# button.net
KiCad netlist of a schematic drawn in Altium Designer
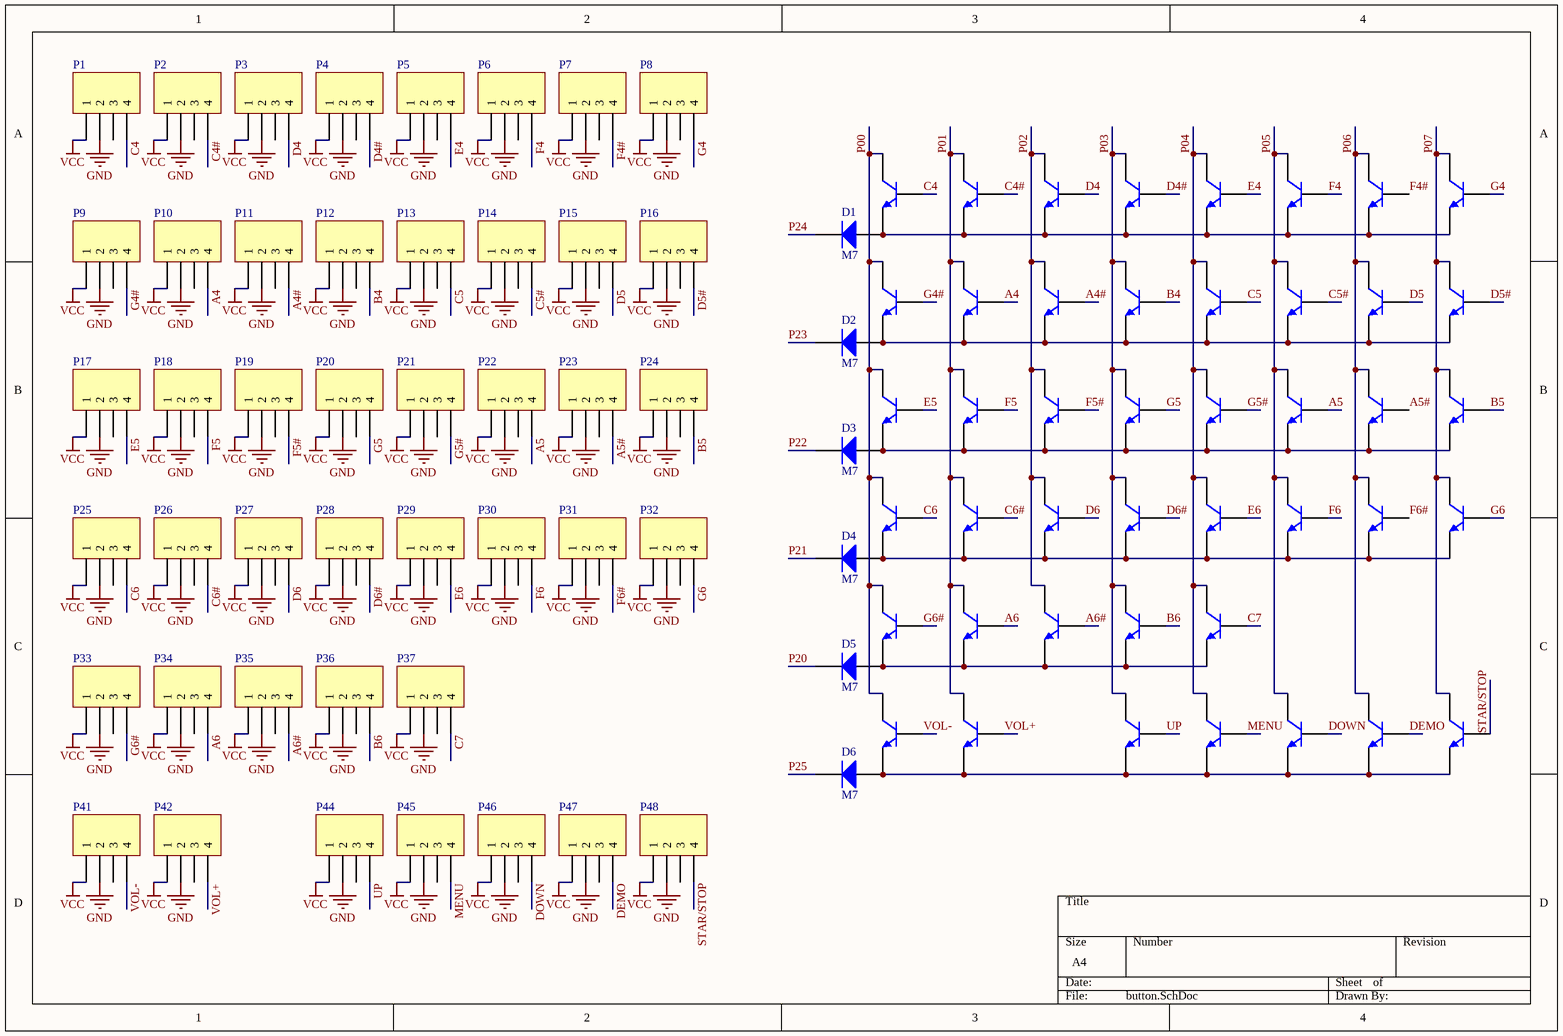
[diagram p0: button.SchDoc]

(export (version "E")
  (design (tool "Eeschema 10.0.6"))
  (components
    (comp (ref "D1")
      (value "M7")
      (footprint "SMA(DO-214AC)_S1")
      (description "二极管")
      (libsource (lib "Miscellaneous Devices LC") (part "SMA(DO-214AC) M7"))
    )
    (comp (ref "D2")
      (value "M7")
      (footprint "SMA(DO-214AC)_S1")
      (description "二极管")
      (libsource (lib "Miscellaneous Devices LC") (part "SMA(DO-214AC) M7"))
    )
    (comp (ref "D3")
      (value "M7")
      (footprint "SMA(DO-214AC)_S1")
      (description "二极管")
      (libsource (lib "Miscellaneous Devices LC") (part "SMA(DO-214AC) M7"))
    )
    (comp (ref "D4")
      (value "M7")
      (footprint "SMA(DO-214AC)_S1")
      (description "二极管")
      (libsource (lib "Miscellaneous Devices LC") (part "SMA(DO-214AC) M7"))
    )
    (comp (ref "D5")
      (value "M7")
      (footprint "SMA(DO-214AC)_S1")
      (description "二极管")
      (libsource (lib "Miscellaneous Devices LC") (part "SMA(DO-214AC) M7"))
    )
    (comp (ref "D6")
      (value "M7")
      (footprint "SMA(DO-214AC)_S1")
      (description "二极管")
      (libsource (lib "Miscellaneous Devices LC") (part "SMA(DO-214AC) M7"))
    )
    (comp (ref "P1")
      (value "Header 4")
      (footprint "FPC1.0-2H-WS-4P")
      (description "Header, 4-Pin")
      (fields (field (name "PUBLISHER") "Altium Limited"))
      (libsource (lib "Miscellaneous Connectors") (part "Header 4"))
    )
    (comp (ref "P2")
      (value "Header 4")
      (footprint "FPC1.0-2H-WS-4P")
      (description "Header, 4-Pin")
      (fields (field (name "PUBLISHER") "Altium Limited"))
      (libsource (lib "Miscellaneous Connectors") (part "Header 4"))
    )
    (comp (ref "P3")
      (value "Header 4")
      (footprint "FPC1.0-2H-WS-4P")
      (description "Header, 4-Pin")
      (fields (field (name "PUBLISHER") "Altium Limited"))
      (libsource (lib "Miscellaneous Connectors") (part "Header 4"))
    )
    (comp (ref "P4")
      (value "Header 4")
      (footprint "FPC1.0-2H-WS-4P")
      (description "Header, 4-Pin")
      (fields (field (name "PUBLISHER") "Altium Limited"))
      (libsource (lib "Miscellaneous Connectors") (part "Header 4"))
    )
    (comp (ref "P5")
      (value "Header 4")
      (footprint "FPC1.0-2H-WS-4P")
      (description "Header, 4-Pin")
      (fields (field (name "PUBLISHER") "Altium Limited"))
      (libsource (lib "Miscellaneous Connectors") (part "Header 4"))
    )
    (comp (ref "P6")
      (value "Header 4")
      (footprint "FPC1.0-2H-WS-4P")
      (description "Header, 4-Pin")
      (fields (field (name "PUBLISHER") "Altium Limited"))
      (libsource (lib "Miscellaneous Connectors") (part "Header 4"))
    )
    (comp (ref "P7")
      (value "Header 4")
      (footprint "FPC1.0-2H-WS-4P")
      (description "Header, 4-Pin")
      (fields (field (name "PUBLISHER") "Altium Limited"))
      (libsource (lib "Miscellaneous Connectors") (part "Header 4"))
    )
    (comp (ref "P8")
      (value "Header 4")
      (footprint "FPC1.0-2H-WS-4P")
      (description "Header, 4-Pin")
      (fields (field (name "PUBLISHER") "Altium Limited"))
      (libsource (lib "Miscellaneous Connectors") (part "Header 4"))
    )
    (comp (ref "P9")
      (value "Header 4")
      (footprint "FPC1.0-2H-WS-4P")
      (description "Header, 4-Pin")
      (fields (field (name "PUBLISHER") "Altium Limited"))
      (libsource (lib "Miscellaneous Connectors") (part "Header 4"))
    )
    (comp (ref "P10")
      (value "Header 4")
      (footprint "FPC1.0-2H-WS-4P")
      (description "Header, 4-Pin")
      (fields (field (name "PUBLISHER") "Altium Limited"))
      (libsource (lib "Miscellaneous Connectors") (part "Header 4"))
    )
    (comp (ref "P11")
      (value "Header 4")
      (footprint "FPC1.0-2H-WS-4P")
      (description "Header, 4-Pin")
      (fields (field (name "PUBLISHER") "Altium Limited"))
      (libsource (lib "Miscellaneous Connectors") (part "Header 4"))
    )
    (comp (ref "P12")
      (value "Header 4")
      (footprint "FPC1.0-2H-WS-4P")
      (description "Header, 4-Pin")
      (fields (field (name "PUBLISHER") "Altium Limited"))
      (libsource (lib "Miscellaneous Connectors") (part "Header 4"))
    )
    (comp (ref "P13")
      (value "Header 4")
      (footprint "FPC1.0-2H-WS-4P")
      (description "Header, 4-Pin")
      (fields (field (name "PUBLISHER") "Altium Limited"))
      (libsource (lib "Miscellaneous Connectors") (part "Header 4"))
    )
    (comp (ref "P14")
      (value "Header 4")
      (footprint "FPC1.0-2H-WS-4P")
      (description "Header, 4-Pin")
      (fields (field (name "PUBLISHER") "Altium Limited"))
      (libsource (lib "Miscellaneous Connectors") (part "Header 4"))
    )
    (comp (ref "P15")
      (value "Header 4")
      (footprint "FPC1.0-2H-WS-4P")
      (description "Header, 4-Pin")
      (fields (field (name "PUBLISHER") "Altium Limited"))
      (libsource (lib "Miscellaneous Connectors") (part "Header 4"))
    )
    (comp (ref "P16")
      (value "Header 4")
      (footprint "FPC1.0-2H-WS-4P")
      (description "Header, 4-Pin")
      (fields (field (name "PUBLISHER") "Altium Limited"))
      (libsource (lib "Miscellaneous Connectors") (part "Header 4"))
    )
    (comp (ref "P17")
      (value "Header 4")
      (footprint "FPC1.0-2H-WS-4P")
      (description "Header, 4-Pin")
      (fields (field (name "PUBLISHER") "Altium Limited"))
      (libsource (lib "Miscellaneous Connectors") (part "Header 4"))
    )
    (comp (ref "P18")
      (value "Header 4")
      (footprint "FPC1.0-2H-WS-4P")
      (description "Header, 4-Pin")
      (fields (field (name "PUBLISHER") "Altium Limited"))
      (libsource (lib "Miscellaneous Connectors") (part "Header 4"))
    )
    (comp (ref "P19")
      (value "Header 4")
      (footprint "FPC1.0-2H-WS-4P")
      (description "Header, 4-Pin")
      (fields (field (name "PUBLISHER") "Altium Limited"))
      (libsource (lib "Miscellaneous Connectors") (part "Header 4"))
    )
    (comp (ref "P20")
      (value "Header 4")
      (footprint "FPC1.0-2H-WS-4P")
      (description "Header, 4-Pin")
      (fields (field (name "PUBLISHER") "Altium Limited"))
      (libsource (lib "Miscellaneous Connectors") (part "Header 4"))
    )
    (comp (ref "P21")
      (value "Header 4")
      (footprint "FPC1.0-2H-WS-4P")
      (description "Header, 4-Pin")
      (fields (field (name "PUBLISHER") "Altium Limited"))
      (libsource (lib "Miscellaneous Connectors") (part "Header 4"))
    )
    (comp (ref "P22")
      (value "Header 4")
      (footprint "FPC1.0-2H-WS-4P")
      (description "Header, 4-Pin")
      (fields (field (name "PUBLISHER") "Altium Limited"))
      (libsource (lib "Miscellaneous Connectors") (part "Header 4"))
    )
    (comp (ref "P23")
      (value "Header 4")
      (footprint "FPC1.0-2H-WS-4P")
      (description "Header, 4-Pin")
      (fields (field (name "PUBLISHER") "Altium Limited"))
      (libsource (lib "Miscellaneous Connectors") (part "Header 4"))
    )
    (comp (ref "P24")
      (value "Header 4")
      (footprint "FPC1.0-2H-WS-4P")
      (description "Header, 4-Pin")
      (fields (field (name "PUBLISHER") "Altium Limited"))
      (libsource (lib "Miscellaneous Connectors") (part "Header 4"))
    )
    (comp (ref "P25")
      (value "Header 4")
      (footprint "FPC1.0-2H-WS-4P")
      (description "Header, 4-Pin")
      (fields (field (name "PUBLISHER") "Altium Limited"))
      (libsource (lib "Miscellaneous Connectors") (part "Header 4"))
    )
    (comp (ref "P26")
      (value "Header 4")
      (footprint "FPC1.0-2H-WS-4P")
      (description "Header, 4-Pin")
      (fields (field (name "PUBLISHER") "Altium Limited"))
      (libsource (lib "Miscellaneous Connectors") (part "Header 4"))
    )
    (comp (ref "P27")
      (value "Header 4")
      (footprint "FPC1.0-2H-WS-4P")
      (description "Header, 4-Pin")
      (fields (field (name "PUBLISHER") "Altium Limited"))
      (libsource (lib "Miscellaneous Connectors") (part "Header 4"))
    )
    (comp (ref "P28")
      (value "Header 4")
      (footprint "FPC1.0-2H-WS-4P")
      (description "Header, 4-Pin")
      (fields (field (name "PUBLISHER") "Altium Limited"))
      (libsource (lib "Miscellaneous Connectors") (part "Header 4"))
    )
    (comp (ref "P29")
      (value "Header 4")
      (footprint "FPC1.0-2H-WS-4P")
      (description "Header, 4-Pin")
      (fields (field (name "PUBLISHER") "Altium Limited"))
      (libsource (lib "Miscellaneous Connectors") (part "Header 4"))
    )
    (comp (ref "P30")
      (value "Header 4")
      (footprint "FPC1.0-2H-WS-4P")
      (description "Header, 4-Pin")
      (fields (field (name "PUBLISHER") "Altium Limited"))
      (libsource (lib "Miscellaneous Connectors") (part "Header 4"))
    )
    (comp (ref "P31")
      (value "Header 4")
      (footprint "FPC1.0-2H-WS-4P")
      (description "Header, 4-Pin")
      (fields (field (name "PUBLISHER") "Altium Limited"))
      (libsource (lib "Miscellaneous Connectors") (part "Header 4"))
    )
    (comp (ref "P32")
      (value "Header 4")
      (footprint "FPC1.0-2H-WS-4P")
      (description "Header, 4-Pin")
      (fields (field (name "PUBLISHER") "Altium Limited"))
      (libsource (lib "Miscellaneous Connectors") (part "Header 4"))
    )
    (comp (ref "P33")
      (value "Header 4")
      (footprint "FPC1.0-2H-WS-4P")
      (description "Header, 4-Pin")
      (fields (field (name "PUBLISHER") "Altium Limited"))
      (libsource (lib "Miscellaneous Connectors") (part "Header 4"))
    )
    (comp (ref "P34")
      (value "Header 4")
      (footprint "FPC1.0-2H-WS-4P")
      (description "Header, 4-Pin")
      (fields (field (name "PUBLISHER") "Altium Limited"))
      (libsource (lib "Miscellaneous Connectors") (part "Header 4"))
    )
    (comp (ref "P35")
      (value "Header 4")
      (footprint "FPC1.0-2H-WS-4P")
      (description "Header, 4-Pin")
      (fields (field (name "PUBLISHER") "Altium Limited"))
      (libsource (lib "Miscellaneous Connectors") (part "Header 4"))
    )
    (comp (ref "P36")
      (value "Header 4")
      (footprint "FPC1.0-2H-WS-4P")
      (description "Header, 4-Pin")
      (fields (field (name "PUBLISHER") "Altium Limited"))
      (libsource (lib "Miscellaneous Connectors") (part "Header 4"))
    )
    (comp (ref "P37")
      (value "Header 4")
      (footprint "FPC1.0-2H-WS-4P")
      (description "Header, 4-Pin")
      (fields (field (name "PUBLISHER") "Altium Limited"))
      (libsource (lib "Miscellaneous Connectors") (part "Header 4"))
    )
    (comp (ref "P41")
      (value "Header 4")
      (footprint "FPC1.0-2H-WS-4P")
      (description "Header, 4-Pin")
      (fields (field (name "PUBLISHER") "Altium Limited"))
      (libsource (lib "Miscellaneous Connectors") (part "Header 4"))
    )
    (comp (ref "P42")
      (value "Header 4")
      (footprint "FPC1.0-2H-WS-4P")
      (description "Header, 4-Pin")
      (fields (field (name "PUBLISHER") "Altium Limited"))
      (libsource (lib "Miscellaneous Connectors") (part "Header 4"))
    )
    (comp (ref "P44")
      (value "Header 4")
      (footprint "FPC1.0-2H-WS-4P")
      (description "Header, 4-Pin")
      (fields (field (name "PUBLISHER") "Altium Limited"))
      (libsource (lib "Miscellaneous Connectors") (part "Header 4"))
    )
    (comp (ref "P45")
      (value "Header 4")
      (footprint "FPC1.0-2H-WS-4P")
      (description "Header, 4-Pin")
      (fields (field (name "PUBLISHER") "Altium Limited"))
      (libsource (lib "Miscellaneous Connectors") (part "Header 4"))
    )
    (comp (ref "P46")
      (value "Header 4")
      (footprint "FPC1.0-2H-WS-4P")
      (description "Header, 4-Pin")
      (fields (field (name "PUBLISHER") "Altium Limited"))
      (libsource (lib "Miscellaneous Connectors") (part "Header 4"))
    )
    (comp (ref "P47")
      (value "Header 4")
      (footprint "FPC1.0-2H-WS-4P")
      (description "Header, 4-Pin")
      (fields (field (name "PUBLISHER") "Altium Limited"))
      (libsource (lib "Miscellaneous Connectors") (part "Header 4"))
    )
    (comp (ref "P48")
      (value "Header 4")
      (footprint "FPC1.0-2H-WS-4P")
      (description "Header, 4-Pin")
      (fields (field (name "PUBLISHER") "Altium Limited"))
      (libsource (lib "Miscellaneous Connectors") (part "Header 4"))
    )
    (comp (ref "Q1")
      (value "SS8050 Y1")
      (footprint "SOT-23(SOT-23-3)")
      (description "三极管")
      (libsource (lib "Miscellaneous Devices LC") (part "SOT-23 SS8050 Y1"))
    )
    (comp (ref "Q2")
      (value "SS8050 Y1")
      (footprint "SOT-23(SOT-23-3)")
      (description "三极管")
      (libsource (lib "Miscellaneous Devices LC") (part "SOT-23 SS8050 Y1"))
    )
    (comp (ref "Q3")
      (value "SS8050 Y1")
      (footprint "SOT-23(SOT-23-3)")
      (description "三极管")
      (libsource (lib "Miscellaneous Devices LC") (part "SOT-23 SS8050 Y1"))
    )
    (comp (ref "Q4")
      (value "SS8050 Y1")
      (footprint "SOT-23(SOT-23-3)")
      (description "三极管")
      (libsource (lib "Miscellaneous Devices LC") (part "SOT-23 SS8050 Y1"))
    )
    (comp (ref "Q5")
      (value "SS8050 Y1")
      (footprint "SOT-23(SOT-23-3)")
      (description "三极管")
      (libsource (lib "Miscellaneous Devices LC") (part "SOT-23 SS8050 Y1"))
    )
    (comp (ref "Q6")
      (value "SS8050 Y1")
      (footprint "SOT-23(SOT-23-3)")
      (description "三极管")
      (libsource (lib "Miscellaneous Devices LC") (part "SOT-23 SS8050 Y1"))
    )
    (comp (ref "Q7")
      (value "SS8050 Y1")
      (footprint "SOT-23(SOT-23-3)")
      (description "三极管")
      (libsource (lib "Miscellaneous Devices LC") (part "SOT-23 SS8050 Y1"))
    )
    (comp (ref "Q8")
      (value "SS8050 Y1")
      (footprint "SOT-23(SOT-23-3)")
      (description "三极管")
      (libsource (lib "Miscellaneous Devices LC") (part "SOT-23 SS8050 Y1"))
    )
    (comp (ref "Q9")
      (value "SS8050 Y1")
      (footprint "SOT-23(SOT-23-3)")
      (description "三极管")
      (libsource (lib "Miscellaneous Devices LC") (part "SOT-23 SS8050 Y1"))
    )
    (comp (ref "Q10")
      (value "SS8050 Y1")
      (footprint "SOT-23(SOT-23-3)")
      (description "三极管")
      (libsource (lib "Miscellaneous Devices LC") (part "SOT-23 SS8050 Y1"))
    )
    (comp (ref "Q11")
      (value "SS8050 Y1")
      (footprint "SOT-23(SOT-23-3)")
      (description "三极管")
      (libsource (lib "Miscellaneous Devices LC") (part "SOT-23 SS8050 Y1"))
    )
    (comp (ref "Q12")
      (value "SS8050 Y1")
      (footprint "SOT-23(SOT-23-3)")
      (description "三极管")
      (libsource (lib "Miscellaneous Devices LC") (part "SOT-23 SS8050 Y1"))
    )
    (comp (ref "Q13")
      (value "SS8050 Y1")
      (footprint "SOT-23(SOT-23-3)")
      (description "三极管")
      (libsource (lib "Miscellaneous Devices LC") (part "SOT-23 SS8050 Y1"))
    )
    (comp (ref "Q14")
      (value "SS8050 Y1")
      (footprint "SOT-23(SOT-23-3)")
      (description "三极管")
      (libsource (lib "Miscellaneous Devices LC") (part "SOT-23 SS8050 Y1"))
    )
    (comp (ref "Q15")
      (value "SS8050 Y1")
      (footprint "SOT-23(SOT-23-3)")
      (description "三极管")
      (libsource (lib "Miscellaneous Devices LC") (part "SOT-23 SS8050 Y1"))
    )
    (comp (ref "Q16")
      (value "SS8050 Y1")
      (footprint "SOT-23(SOT-23-3)")
      (description "三极管")
      (libsource (lib "Miscellaneous Devices LC") (part "SOT-23 SS8050 Y1"))
    )
    (comp (ref "Q17")
      (value "SS8050 Y1")
      (footprint "SOT-23(SOT-23-3)")
      (description "三极管")
      (libsource (lib "Miscellaneous Devices LC") (part "SOT-23 SS8050 Y1"))
    )
    (comp (ref "Q18")
      (value "SS8050 Y1")
      (footprint "SOT-23(SOT-23-3)")
      (description "三极管")
      (libsource (lib "Miscellaneous Devices LC") (part "SOT-23 SS8050 Y1"))
    )
    (comp (ref "Q19")
      (value "SS8050 Y1")
      (footprint "SOT-23(SOT-23-3)")
      (description "三极管")
      (libsource (lib "Miscellaneous Devices LC") (part "SOT-23 SS8050 Y1"))
    )
    (comp (ref "Q20")
      (value "SS8050 Y1")
      (footprint "SOT-23(SOT-23-3)")
      (description "三极管")
      (libsource (lib "Miscellaneous Devices LC") (part "SOT-23 SS8050 Y1"))
    )
    (comp (ref "Q21")
      (value "SS8050 Y1")
      (footprint "SOT-23(SOT-23-3)")
      (description "三极管")
      (libsource (lib "Miscellaneous Devices LC") (part "SOT-23 SS8050 Y1"))
    )
    (comp (ref "Q22")
      (value "SS8050 Y1")
      (footprint "SOT-23(SOT-23-3)")
      (description "三极管")
      (libsource (lib "Miscellaneous Devices LC") (part "SOT-23 SS8050 Y1"))
    )
    (comp (ref "Q23")
      (value "SS8050 Y1")
      (footprint "SOT-23(SOT-23-3)")
      (description "三极管")
      (libsource (lib "Miscellaneous Devices LC") (part "SOT-23 SS8050 Y1"))
    )
    (comp (ref "Q24")
      (value "SS8050 Y1")
      (footprint "SOT-23(SOT-23-3)")
      (description "三极管")
      (libsource (lib "Miscellaneous Devices LC") (part "SOT-23 SS8050 Y1"))
    )
    (comp (ref "Q25")
      (value "SS8050 Y1")
      (footprint "SOT-23(SOT-23-3)")
      (description "三极管")
      (libsource (lib "Miscellaneous Devices LC") (part "SOT-23 SS8050 Y1"))
    )
    (comp (ref "Q26")
      (value "SS8050 Y1")
      (footprint "SOT-23(SOT-23-3)")
      (description "三极管")
      (libsource (lib "Miscellaneous Devices LC") (part "SOT-23 SS8050 Y1"))
    )
    (comp (ref "Q27")
      (value "SS8050 Y1")
      (footprint "SOT-23(SOT-23-3)")
      (description "三极管")
      (libsource (lib "Miscellaneous Devices LC") (part "SOT-23 SS8050 Y1"))
    )
    (comp (ref "Q28")
      (value "SS8050 Y1")
      (footprint "SOT-23(SOT-23-3)")
      (description "三极管")
      (libsource (lib "Miscellaneous Devices LC") (part "SOT-23 SS8050 Y1"))
    )
    (comp (ref "Q29")
      (value "SS8050 Y1")
      (footprint "SOT-23(SOT-23-3)")
      (description "三极管")
      (libsource (lib "Miscellaneous Devices LC") (part "SOT-23 SS8050 Y1"))
    )
    (comp (ref "Q30")
      (value "SS8050 Y1")
      (footprint "SOT-23(SOT-23-3)")
      (description "三极管")
      (libsource (lib "Miscellaneous Devices LC") (part "SOT-23 SS8050 Y1"))
    )
    (comp (ref "Q31")
      (value "SS8050 Y1")
      (footprint "SOT-23(SOT-23-3)")
      (description "三极管")
      (libsource (lib "Miscellaneous Devices LC") (part "SOT-23 SS8050 Y1"))
    )
    (comp (ref "Q32")
      (value "SS8050 Y1")
      (footprint "SOT-23(SOT-23-3)")
      (description "三极管")
      (libsource (lib "Miscellaneous Devices LC") (part "SOT-23 SS8050 Y1"))
    )
    (comp (ref "Q33")
      (value "SS8050 Y1")
      (footprint "SOT-23(SOT-23-3)")
      (description "三极管")
      (libsource (lib "Miscellaneous Devices LC") (part "SOT-23 SS8050 Y1"))
    )
    (comp (ref "Q34")
      (value "SS8050 Y1")
      (footprint "SOT-23(SOT-23-3)")
      (description "三极管")
      (libsource (lib "Miscellaneous Devices LC") (part "SOT-23 SS8050 Y1"))
    )
    (comp (ref "Q35")
      (value "SS8050 Y1")
      (footprint "SOT-23(SOT-23-3)")
      (description "三极管")
      (libsource (lib "Miscellaneous Devices LC") (part "SOT-23 SS8050 Y1"))
    )
    (comp (ref "Q36")
      (value "SS8050 Y1")
      (footprint "SOT-23(SOT-23-3)")
      (description "三极管")
      (libsource (lib "Miscellaneous Devices LC") (part "SOT-23 SS8050 Y1"))
    )
    (comp (ref "Q37")
      (value "SS8050 Y1")
      (footprint "SOT-23(SOT-23-3)")
      (description "三极管")
      (libsource (lib "Miscellaneous Devices LC") (part "SOT-23 SS8050 Y1"))
    )
    (comp (ref "Q38")
      (value "SS8050 Y1")
      (footprint "SOT-23(SOT-23-3)")
      (description "三极管")
      (libsource (lib "Miscellaneous Devices LC") (part "SOT-23 SS8050 Y1"))
    )
    (comp (ref "Q39")
      (value "SS8050 Y1")
      (footprint "SOT-23(SOT-23-3)")
      (description "三极管")
      (libsource (lib "Miscellaneous Devices LC") (part "SOT-23 SS8050 Y1"))
    )
    (comp (ref "Q40")
      (value "SS8050 Y1")
      (footprint "SOT-23(SOT-23-3)")
      (description "三极管")
      (libsource (lib "Miscellaneous Devices LC") (part "SOT-23 SS8050 Y1"))
    )
    (comp (ref "Q41")
      (value "SS8050 Y1")
      (footprint "SOT-23(SOT-23-3)")
      (description "三极管")
      (libsource (lib "Miscellaneous Devices LC") (part "SOT-23 SS8050 Y1"))
    )
    (comp (ref "Q42")
      (value "SS8050 Y1")
      (footprint "SOT-23(SOT-23-3)")
      (description "三极管")
      (libsource (lib "Miscellaneous Devices LC") (part "SOT-23 SS8050 Y1"))
    )
    (comp (ref "Q43")
      (value "SS8050 Y1")
      (footprint "SOT-23(SOT-23-3)")
      (description "三极管")
      (libsource (lib "Miscellaneous Devices LC") (part "SOT-23 SS8050 Y1"))
    )
    (comp (ref "Q44")
      (value "SS8050 Y1")
      (footprint "SOT-23(SOT-23-3)")
      (description "三极管")
      (libsource (lib "Miscellaneous Devices LC") (part "SOT-23 SS8050 Y1"))
    )
  )
  (nets
    (net (code "1") (name "/A4") (class "Default")
      (node (ref "P10") (pin "4") (pinfunction "4_4") (pintype "passive"))
      (node (ref "Q10") (pin "1") (pinfunction "B_1") (pintype "passive"))
    )
    (net (code "2") (name "/A4#") (class "Default")
      (node (ref "P11") (pin "4") (pinfunction "4_4") (pintype "passive"))
      (node (ref "Q11") (pin "1") (pinfunction "B_1") (pintype "passive"))
    )
    (net (code "3") (name "/A5") (class "Default")
      (node (ref "P22") (pin "4") (pinfunction "4_4") (pintype "passive"))
      (node (ref "Q22") (pin "1") (pinfunction "B_1") (pintype "passive"))
    )
    (net (code "4") (name "/A5#") (class "Default")
      (node (ref "P23") (pin "4") (pinfunction "4_4") (pintype "passive"))
      (node (ref "Q23") (pin "1") (pinfunction "B_1") (pintype "passive"))
    )
    (net (code "5") (name "/A6") (class "Default")
      (node (ref "P34") (pin "4") (pinfunction "4_4") (pintype "passive"))
      (node (ref "Q34") (pin "1") (pinfunction "B_1") (pintype "passive"))
    )
    (net (code "6") (name "/A6#") (class "Default")
      (node (ref "P35") (pin "4") (pinfunction "4_4") (pintype "passive"))
      (node (ref "Q35") (pin "1") (pinfunction "B_1") (pintype "passive"))
    )
    (net (code "7") (name "/B4") (class "Default")
      (node (ref "P12") (pin "4") (pinfunction "4_4") (pintype "passive"))
      (node (ref "Q12") (pin "1") (pinfunction "B_1") (pintype "passive"))
    )
    (net (code "8") (name "/B5") (class "Default")
      (node (ref "P24") (pin "4") (pinfunction "4_4") (pintype "passive"))
      (node (ref "Q24") (pin "1") (pinfunction "B_1") (pintype "passive"))
    )
    (net (code "9") (name "/B6") (class "Default")
      (node (ref "P36") (pin "4") (pinfunction "4_4") (pintype "passive"))
      (node (ref "Q36") (pin "1") (pinfunction "B_1") (pintype "passive"))
    )
    (net (code "10") (name "/C4") (class "Default")
      (node (ref "P1") (pin "4") (pinfunction "4_4") (pintype "passive"))
      (node (ref "Q1") (pin "1") (pinfunction "B_1") (pintype "passive"))
    )
    (net (code "11") (name "/C4#") (class "Default")
      (node (ref "P2") (pin "4") (pinfunction "4_4") (pintype "passive"))
      (node (ref "Q2") (pin "1") (pinfunction "B_1") (pintype "passive"))
    )
    (net (code "12") (name "/C5") (class "Default")
      (node (ref "P13") (pin "4") (pinfunction "4_4") (pintype "passive"))
      (node (ref "Q13") (pin "1") (pinfunction "B_1") (pintype "passive"))
    )
    (net (code "13") (name "/C5#") (class "Default")
      (node (ref "P14") (pin "4") (pinfunction "4_4") (pintype "passive"))
      (node (ref "Q14") (pin "1") (pinfunction "B_1") (pintype "passive"))
    )
    (net (code "14") (name "/C6") (class "Default")
      (node (ref "P25") (pin "4") (pinfunction "4_4") (pintype "passive"))
      (node (ref "Q25") (pin "1") (pinfunction "B_1") (pintype "passive"))
    )
    (net (code "15") (name "/C6#") (class "Default")
      (node (ref "P26") (pin "4") (pinfunction "4_4") (pintype "passive"))
      (node (ref "Q26") (pin "1") (pinfunction "B_1") (pintype "passive"))
    )
    (net (code "16") (name "/C7") (class "Default")
      (node (ref "P37") (pin "4") (pinfunction "4_4") (pintype "passive"))
      (node (ref "Q37") (pin "1") (pinfunction "B_1") (pintype "passive"))
    )
    (net (code "17") (name "/D4") (class "Default")
      (node (ref "P3") (pin "4") (pinfunction "4_4") (pintype "passive"))
      (node (ref "Q3") (pin "1") (pinfunction "B_1") (pintype "passive"))
    )
    (net (code "18") (name "/D4#") (class "Default")
      (node (ref "P4") (pin "4") (pinfunction "4_4") (pintype "passive"))
      (node (ref "Q4") (pin "1") (pinfunction "B_1") (pintype "passive"))
    )
    (net (code "19") (name "/D5") (class "Default")
      (node (ref "P15") (pin "4") (pinfunction "4_4") (pintype "passive"))
      (node (ref "Q15") (pin "1") (pinfunction "B_1") (pintype "passive"))
    )
    (net (code "20") (name "/D5#") (class "Default")
      (node (ref "P16") (pin "4") (pinfunction "4_4") (pintype "passive"))
      (node (ref "Q16") (pin "1") (pinfunction "B_1") (pintype "passive"))
    )
    (net (code "21") (name "/D6") (class "Default")
      (node (ref "P27") (pin "4") (pinfunction "4_4") (pintype "passive"))
      (node (ref "Q27") (pin "1") (pinfunction "B_1") (pintype "passive"))
    )
    (net (code "22") (name "/D6#") (class "Default")
      (node (ref "P28") (pin "4") (pinfunction "4_4") (pintype "passive"))
      (node (ref "Q28") (pin "1") (pinfunction "B_1") (pintype "passive"))
    )
    (net (code "23") (name "/DEMO") (class "Default")
      (node (ref "P47") (pin "4") (pinfunction "4_4") (pintype "passive"))
      (node (ref "Q43") (pin "1") (pinfunction "B_1") (pintype "passive"))
    )
    (net (code "24") (name "/DOWN") (class "Default")
      (node (ref "P46") (pin "4") (pinfunction "4_4") (pintype "passive"))
      (node (ref "Q42") (pin "1") (pinfunction "B_1") (pintype "passive"))
    )
    (net (code "25") (name "/E4") (class "Default")
      (node (ref "P5") (pin "4") (pinfunction "4_4") (pintype "passive"))
      (node (ref "Q5") (pin "1") (pinfunction "B_1") (pintype "passive"))
    )
    (net (code "26") (name "/E5") (class "Default")
      (node (ref "P17") (pin "4") (pinfunction "4_4") (pintype "passive"))
      (node (ref "Q17") (pin "1") (pinfunction "B_1") (pintype "passive"))
    )
    (net (code "27") (name "/E6") (class "Default")
      (node (ref "P29") (pin "4") (pinfunction "4_4") (pintype "passive"))
      (node (ref "Q29") (pin "1") (pinfunction "B_1") (pintype "passive"))
    )
    (net (code "28") (name "/F4") (class "Default")
      (node (ref "P6") (pin "4") (pinfunction "4_4") (pintype "passive"))
      (node (ref "Q6") (pin "1") (pinfunction "B_1") (pintype "passive"))
    )
    (net (code "29") (name "/F4#") (class "Default")
      (node (ref "P7") (pin "4") (pinfunction "4_4") (pintype "passive"))
      (node (ref "Q7") (pin "1") (pinfunction "B_1") (pintype "passive"))
    )
    (net (code "30") (name "/F5") (class "Default")
      (node (ref "P18") (pin "4") (pinfunction "4_4") (pintype "passive"))
      (node (ref "Q18") (pin "1") (pinfunction "B_1") (pintype "passive"))
    )
    (net (code "31") (name "/F5#") (class "Default")
      (node (ref "P19") (pin "4") (pinfunction "4_4") (pintype "passive"))
      (node (ref "Q19") (pin "1") (pinfunction "B_1") (pintype "passive"))
    )
    (net (code "32") (name "/F6") (class "Default")
      (node (ref "P30") (pin "4") (pinfunction "4_4") (pintype "passive"))
      (node (ref "Q30") (pin "1") (pinfunction "B_1") (pintype "passive"))
    )
    (net (code "33") (name "/F6#") (class "Default")
      (node (ref "P31") (pin "4") (pinfunction "4_4") (pintype "passive"))
      (node (ref "Q31") (pin "1") (pinfunction "B_1") (pintype "passive"))
    )
    (net (code "34") (name "/G4") (class "Default")
      (node (ref "P8") (pin "4") (pinfunction "4_4") (pintype "passive"))
      (node (ref "Q8") (pin "1") (pinfunction "B_1") (pintype "passive"))
    )
    (net (code "35") (name "/G4#") (class "Default")
      (node (ref "P9") (pin "4") (pinfunction "4_4") (pintype "passive"))
      (node (ref "Q9") (pin "1") (pinfunction "B_1") (pintype "passive"))
    )
    (net (code "36") (name "/G5") (class "Default")
      (node (ref "P20") (pin "4") (pinfunction "4_4") (pintype "passive"))
      (node (ref "Q20") (pin "1") (pinfunction "B_1") (pintype "passive"))
    )
    (net (code "37") (name "/G5#") (class "Default")
      (node (ref "P21") (pin "4") (pinfunction "4_4") (pintype "passive"))
      (node (ref "Q21") (pin "1") (pinfunction "B_1") (pintype "passive"))
    )
    (net (code "38") (name "/G6") (class "Default")
      (node (ref "P32") (pin "4") (pinfunction "4_4") (pintype "passive"))
      (node (ref "Q32") (pin "1") (pinfunction "B_1") (pintype "passive"))
    )
    (net (code "39") (name "/G6#") (class "Default")
      (node (ref "P33") (pin "4") (pinfunction "4_4") (pintype "passive"))
      (node (ref "Q33") (pin "1") (pinfunction "B_1") (pintype "passive"))
    )
    (net (code "40") (name "/MENU") (class "Default")
      (node (ref "P45") (pin "4") (pinfunction "4_4") (pintype "passive"))
      (node (ref "Q41") (pin "1") (pinfunction "B_1") (pintype "passive"))
    )
    (net (code "41") (name "/P00") (class "Default")
      (node (ref "Q1") (pin "3") (pinfunction "C_3") (pintype "passive"))
      (node (ref "Q17") (pin "3") (pinfunction "C_3") (pintype "passive"))
      (node (ref "Q25") (pin "3") (pinfunction "C_3") (pintype "passive"))
      (node (ref "Q33") (pin "3") (pinfunction "C_3") (pintype "passive"))
      (node (ref "Q38") (pin "3") (pinfunction "C_3") (pintype "passive"))
      (node (ref "Q9") (pin "3") (pinfunction "C_3") (pintype "passive"))
    )
    (net (code "42") (name "/P01") (class "Default")
      (node (ref "Q10") (pin "3") (pinfunction "C_3") (pintype "passive"))
      (node (ref "Q18") (pin "3") (pinfunction "C_3") (pintype "passive"))
      (node (ref "Q2") (pin "3") (pinfunction "C_3") (pintype "passive"))
      (node (ref "Q26") (pin "3") (pinfunction "C_3") (pintype "passive"))
      (node (ref "Q34") (pin "3") (pinfunction "C_3") (pintype "passive"))
      (node (ref "Q39") (pin "3") (pinfunction "C_3") (pintype "passive"))
    )
    (net (code "43") (name "/P02") (class "Default")
      (node (ref "Q11") (pin "3") (pinfunction "C_3") (pintype "passive"))
      (node (ref "Q19") (pin "3") (pinfunction "C_3") (pintype "passive"))
      (node (ref "Q27") (pin "3") (pinfunction "C_3") (pintype "passive"))
      (node (ref "Q3") (pin "3") (pinfunction "C_3") (pintype "passive"))
      (node (ref "Q35") (pin "3") (pinfunction "C_3") (pintype "passive"))
    )
    (net (code "44") (name "/P03") (class "Default")
      (node (ref "Q12") (pin "3") (pinfunction "C_3") (pintype "passive"))
      (node (ref "Q20") (pin "3") (pinfunction "C_3") (pintype "passive"))
      (node (ref "Q28") (pin "3") (pinfunction "C_3") (pintype "passive"))
      (node (ref "Q36") (pin "3") (pinfunction "C_3") (pintype "passive"))
      (node (ref "Q4") (pin "3") (pinfunction "C_3") (pintype "passive"))
      (node (ref "Q40") (pin "3") (pinfunction "C_3") (pintype "passive"))
    )
    (net (code "45") (name "/P04") (class "Default")
      (node (ref "Q13") (pin "3") (pinfunction "C_3") (pintype "passive"))
      (node (ref "Q21") (pin "3") (pinfunction "C_3") (pintype "passive"))
      (node (ref "Q29") (pin "3") (pinfunction "C_3") (pintype "passive"))
      (node (ref "Q37") (pin "3") (pinfunction "C_3") (pintype "passive"))
      (node (ref "Q41") (pin "3") (pinfunction "C_3") (pintype "passive"))
      (node (ref "Q5") (pin "3") (pinfunction "C_3") (pintype "passive"))
    )
    (net (code "46") (name "/P05") (class "Default")
      (node (ref "Q14") (pin "3") (pinfunction "C_3") (pintype "passive"))
      (node (ref "Q22") (pin "3") (pinfunction "C_3") (pintype "passive"))
      (node (ref "Q30") (pin "3") (pinfunction "C_3") (pintype "passive"))
      (node (ref "Q42") (pin "3") (pinfunction "C_3") (pintype "passive"))
      (node (ref "Q6") (pin "3") (pinfunction "C_3") (pintype "passive"))
    )
    (net (code "47") (name "/P06") (class "Default")
      (node (ref "Q15") (pin "3") (pinfunction "C_3") (pintype "passive"))
      (node (ref "Q23") (pin "3") (pinfunction "C_3") (pintype "passive"))
      (node (ref "Q31") (pin "3") (pinfunction "C_3") (pintype "passive"))
      (node (ref "Q43") (pin "3") (pinfunction "C_3") (pintype "passive"))
      (node (ref "Q7") (pin "3") (pinfunction "C_3") (pintype "passive"))
    )
    (net (code "48") (name "/P07") (class "Default")
      (node (ref "Q16") (pin "3") (pinfunction "C_3") (pintype "passive"))
      (node (ref "Q24") (pin "3") (pinfunction "C_3") (pintype "passive"))
      (node (ref "Q32") (pin "3") (pinfunction "C_3") (pintype "passive"))
      (node (ref "Q44") (pin "3") (pinfunction "C_3") (pintype "passive"))
      (node (ref "Q8") (pin "3") (pinfunction "C_3") (pintype "passive"))
    )
    (net (code "49") (name "/P20") (class "Default")
      (node (ref "D5") (pin "2") (pinfunction "K_2") (pintype "passive"))
    )
    (net (code "50") (name "/P21") (class "Default")
      (node (ref "D4") (pin "2") (pinfunction "K_2") (pintype "passive"))
    )
    (net (code "51") (name "/P22") (class "Default")
      (node (ref "D3") (pin "2") (pinfunction "K_2") (pintype "passive"))
    )
    (net (code "52") (name "/P23") (class "Default")
      (node (ref "D2") (pin "2") (pinfunction "K_2") (pintype "passive"))
    )
    (net (code "53") (name "/P24") (class "Default")
      (node (ref "D1") (pin "2") (pinfunction "K_2") (pintype "passive"))
    )
    (net (code "54") (name "/P25") (class "Default")
      (node (ref "D6") (pin "2") (pinfunction "K_2") (pintype "passive"))
    )
    (net (code "55") (name "/STAR{slash}STOP") (class "Default")
      (node (ref "P48") (pin "4") (pinfunction "4_4") (pintype "passive"))
      (node (ref "Q44") (pin "1") (pinfunction "B_1") (pintype "passive"))
    )
    (net (code "56") (name "/UP") (class "Default")
      (node (ref "P44") (pin "4") (pinfunction "4_4") (pintype "passive"))
      (node (ref "Q40") (pin "1") (pinfunction "B_1") (pintype "passive"))
    )
    (net (code "57") (name "/VOL+") (class "Default")
      (node (ref "P42") (pin "4") (pinfunction "4_4") (pintype "passive"))
      (node (ref "Q39") (pin "1") (pinfunction "B_1") (pintype "passive"))
    )
    (net (code "58") (name "/VOL-") (class "Default")
      (node (ref "P41") (pin "4") (pinfunction "4_4") (pintype "passive"))
      (node (ref "Q38") (pin "1") (pinfunction "B_1") (pintype "passive"))
    )
    (net (code "59") (name "GND") (class "Default")
      (node (ref "P1") (pin "2") (pinfunction "2_2") (pintype "passive"))
      (node (ref "P10") (pin "2") (pinfunction "2_2") (pintype "passive"))
      (node (ref "P11") (pin "2") (pinfunction "2_2") (pintype "passive"))
      (node (ref "P12") (pin "2") (pinfunction "2_2") (pintype "passive"))
      (node (ref "P13") (pin "2") (pinfunction "2_2") (pintype "passive"))
      (node (ref "P14") (pin "2") (pinfunction "2_2") (pintype "passive"))
      (node (ref "P15") (pin "2") (pinfunction "2_2") (pintype "passive"))
      (node (ref "P16") (pin "2") (pinfunction "2_2") (pintype "passive"))
      (node (ref "P17") (pin "2") (pinfunction "2_2") (pintype "passive"))
      (node (ref "P18") (pin "2") (pinfunction "2_2") (pintype "passive"))
      (node (ref "P19") (pin "2") (pinfunction "2_2") (pintype "passive"))
      (node (ref "P2") (pin "2") (pinfunction "2_2") (pintype "passive"))
      (node (ref "P20") (pin "2") (pinfunction "2_2") (pintype "passive"))
      (node (ref "P21") (pin "2") (pinfunction "2_2") (pintype "passive"))
      (node (ref "P22") (pin "2") (pinfunction "2_2") (pintype "passive"))
      (node (ref "P23") (pin "2") (pinfunction "2_2") (pintype "passive"))
      (node (ref "P24") (pin "2") (pinfunction "2_2") (pintype "passive"))
      (node (ref "P25") (pin "2") (pinfunction "2_2") (pintype "passive"))
      (node (ref "P26") (pin "2") (pinfunction "2_2") (pintype "passive"))
      (node (ref "P27") (pin "2") (pinfunction "2_2") (pintype "passive"))
      (node (ref "P28") (pin "2") (pinfunction "2_2") (pintype "passive"))
      (node (ref "P29") (pin "2") (pinfunction "2_2") (pintype "passive"))
      (node (ref "P3") (pin "2") (pinfunction "2_2") (pintype "passive"))
      (node (ref "P30") (pin "2") (pinfunction "2_2") (pintype "passive"))
      (node (ref "P31") (pin "2") (pinfunction "2_2") (pintype "passive"))
      (node (ref "P32") (pin "2") (pinfunction "2_2") (pintype "passive"))
      (node (ref "P33") (pin "2") (pinfunction "2_2") (pintype "passive"))
      (node (ref "P34") (pin "2") (pinfunction "2_2") (pintype "passive"))
      (node (ref "P35") (pin "2") (pinfunction "2_2") (pintype "passive"))
      (node (ref "P36") (pin "2") (pinfunction "2_2") (pintype "passive"))
      (node (ref "P37") (pin "2") (pinfunction "2_2") (pintype "passive"))
      (node (ref "P4") (pin "2") (pinfunction "2_2") (pintype "passive"))
      (node (ref "P41") (pin "2") (pinfunction "2_2") (pintype "passive"))
      (node (ref "P42") (pin "2") (pinfunction "2_2") (pintype "passive"))
      (node (ref "P44") (pin "2") (pinfunction "2_2") (pintype "passive"))
      (node (ref "P45") (pin "2") (pinfunction "2_2") (pintype "passive"))
      (node (ref "P46") (pin "2") (pinfunction "2_2") (pintype "passive"))
      (node (ref "P47") (pin "2") (pinfunction "2_2") (pintype "passive"))
      (node (ref "P48") (pin "2") (pinfunction "2_2") (pintype "passive"))
      (node (ref "P5") (pin "2") (pinfunction "2_2") (pintype "passive"))
      (node (ref "P6") (pin "2") (pinfunction "2_2") (pintype "passive"))
      (node (ref "P7") (pin "2") (pinfunction "2_2") (pintype "passive"))
      (node (ref "P8") (pin "2") (pinfunction "2_2") (pintype "passive"))
      (node (ref "P9") (pin "2") (pinfunction "2_2") (pintype "passive"))
    )
    (net (code "60") (name "Net-(D1-A)") (class "Default")
      (node (ref "D1") (pin "1") (pinfunction "A_1") (pintype "passive"))
      (node (ref "Q1") (pin "2") (pinfunction "E_2") (pintype "passive"))
      (node (ref "Q2") (pin "2") (pinfunction "E_2") (pintype "passive"))
      (node (ref "Q3") (pin "2") (pinfunction "E_2") (pintype "passive"))
      (node (ref "Q4") (pin "2") (pinfunction "E_2") (pintype "passive"))
      (node (ref "Q5") (pin "2") (pinfunction "E_2") (pintype "passive"))
      (node (ref "Q6") (pin "2") (pinfunction "E_2") (pintype "passive"))
      (node (ref "Q7") (pin "2") (pinfunction "E_2") (pintype "passive"))
      (node (ref "Q8") (pin "2") (pinfunction "E_2") (pintype "passive"))
    )
    (net (code "61") (name "Net-(D2-A)") (class "Default")
      (node (ref "D2") (pin "1") (pinfunction "A_1") (pintype "passive"))
      (node (ref "Q10") (pin "2") (pinfunction "E_2") (pintype "passive"))
      (node (ref "Q11") (pin "2") (pinfunction "E_2") (pintype "passive"))
      (node (ref "Q12") (pin "2") (pinfunction "E_2") (pintype "passive"))
      (node (ref "Q13") (pin "2") (pinfunction "E_2") (pintype "passive"))
      (node (ref "Q14") (pin "2") (pinfunction "E_2") (pintype "passive"))
      (node (ref "Q15") (pin "2") (pinfunction "E_2") (pintype "passive"))
      (node (ref "Q16") (pin "2") (pinfunction "E_2") (pintype "passive"))
      (node (ref "Q9") (pin "2") (pinfunction "E_2") (pintype "passive"))
    )
    (net (code "62") (name "Net-(D3-A)") (class "Default")
      (node (ref "D3") (pin "1") (pinfunction "A_1") (pintype "passive"))
      (node (ref "Q17") (pin "2") (pinfunction "E_2") (pintype "passive"))
      (node (ref "Q18") (pin "2") (pinfunction "E_2") (pintype "passive"))
      (node (ref "Q19") (pin "2") (pinfunction "E_2") (pintype "passive"))
      (node (ref "Q20") (pin "2") (pinfunction "E_2") (pintype "passive"))
      (node (ref "Q21") (pin "2") (pinfunction "E_2") (pintype "passive"))
      (node (ref "Q22") (pin "2") (pinfunction "E_2") (pintype "passive"))
      (node (ref "Q23") (pin "2") (pinfunction "E_2") (pintype "passive"))
      (node (ref "Q24") (pin "2") (pinfunction "E_2") (pintype "passive"))
    )
    (net (code "63") (name "Net-(D4-A)") (class "Default")
      (node (ref "D4") (pin "1") (pinfunction "A_1") (pintype "passive"))
      (node (ref "Q25") (pin "2") (pinfunction "E_2") (pintype "passive"))
      (node (ref "Q26") (pin "2") (pinfunction "E_2") (pintype "passive"))
      (node (ref "Q27") (pin "2") (pinfunction "E_2") (pintype "passive"))
      (node (ref "Q28") (pin "2") (pinfunction "E_2") (pintype "passive"))
      (node (ref "Q29") (pin "2") (pinfunction "E_2") (pintype "passive"))
      (node (ref "Q30") (pin "2") (pinfunction "E_2") (pintype "passive"))
      (node (ref "Q31") (pin "2") (pinfunction "E_2") (pintype "passive"))
      (node (ref "Q32") (pin "2") (pinfunction "E_2") (pintype "passive"))
    )
    (net (code "64") (name "Net-(D5-A)") (class "Default")
      (node (ref "D5") (pin "1") (pinfunction "A_1") (pintype "passive"))
      (node (ref "Q33") (pin "2") (pinfunction "E_2") (pintype "passive"))
      (node (ref "Q34") (pin "2") (pinfunction "E_2") (pintype "passive"))
      (node (ref "Q35") (pin "2") (pinfunction "E_2") (pintype "passive"))
      (node (ref "Q36") (pin "2") (pinfunction "E_2") (pintype "passive"))
      (node (ref "Q37") (pin "2") (pinfunction "E_2") (pintype "passive"))
    )
    (net (code "65") (name "Net-(D6-A)") (class "Default")
      (node (ref "D6") (pin "1") (pinfunction "A_1") (pintype "passive"))
      (node (ref "Q38") (pin "2") (pinfunction "E_2") (pintype "passive"))
      (node (ref "Q39") (pin "2") (pinfunction "E_2") (pintype "passive"))
      (node (ref "Q40") (pin "2") (pinfunction "E_2") (pintype "passive"))
      (node (ref "Q41") (pin "2") (pinfunction "E_2") (pintype "passive"))
      (node (ref "Q42") (pin "2") (pinfunction "E_2") (pintype "passive"))
      (node (ref "Q43") (pin "2") (pinfunction "E_2") (pintype "passive"))
      (node (ref "Q44") (pin "2") (pinfunction "E_2") (pintype "passive"))
    )
    (net (code "66") (name "VCC") (class "Default")
      (node (ref "P1") (pin "1") (pinfunction "1_1") (pintype "passive"))
      (node (ref "P10") (pin "1") (pinfunction "1_1") (pintype "passive"))
      (node (ref "P11") (pin "1") (pinfunction "1_1") (pintype "passive"))
      (node (ref "P12") (pin "1") (pinfunction "1_1") (pintype "passive"))
      (node (ref "P13") (pin "1") (pinfunction "1_1") (pintype "passive"))
      (node (ref "P14") (pin "1") (pinfunction "1_1") (pintype "passive"))
      (node (ref "P15") (pin "1") (pinfunction "1_1") (pintype "passive"))
      (node (ref "P16") (pin "1") (pinfunction "1_1") (pintype "passive"))
      (node (ref "P17") (pin "1") (pinfunction "1_1") (pintype "passive"))
      (node (ref "P18") (pin "1") (pinfunction "1_1") (pintype "passive"))
      (node (ref "P19") (pin "1") (pinfunction "1_1") (pintype "passive"))
      (node (ref "P2") (pin "1") (pinfunction "1_1") (pintype "passive"))
      (node (ref "P20") (pin "1") (pinfunction "1_1") (pintype "passive"))
      (node (ref "P21") (pin "1") (pinfunction "1_1") (pintype "passive"))
      (node (ref "P22") (pin "1") (pinfunction "1_1") (pintype "passive"))
      (node (ref "P23") (pin "1") (pinfunction "1_1") (pintype "passive"))
      (node (ref "P24") (pin "1") (pinfunction "1_1") (pintype "passive"))
      (node (ref "P25") (pin "1") (pinfunction "1_1") (pintype "passive"))
      (node (ref "P26") (pin "1") (pinfunction "1_1") (pintype "passive"))
      (node (ref "P27") (pin "1") (pinfunction "1_1") (pintype "passive"))
      (node (ref "P28") (pin "1") (pinfunction "1_1") (pintype "passive"))
      (node (ref "P29") (pin "1") (pinfunction "1_1") (pintype "passive"))
      (node (ref "P3") (pin "1") (pinfunction "1_1") (pintype "passive"))
      (node (ref "P30") (pin "1") (pinfunction "1_1") (pintype "passive"))
      (node (ref "P31") (pin "1") (pinfunction "1_1") (pintype "passive"))
      (node (ref "P32") (pin "1") (pinfunction "1_1") (pintype "passive"))
      (node (ref "P33") (pin "1") (pinfunction "1_1") (pintype "passive"))
      (node (ref "P34") (pin "1") (pinfunction "1_1") (pintype "passive"))
      (node (ref "P35") (pin "1") (pinfunction "1_1") (pintype "passive"))
      (node (ref "P36") (pin "1") (pinfunction "1_1") (pintype "passive"))
      (node (ref "P37") (pin "1") (pinfunction "1_1") (pintype "passive"))
      (node (ref "P4") (pin "1") (pinfunction "1_1") (pintype "passive"))
      (node (ref "P41") (pin "1") (pinfunction "1_1") (pintype "passive"))
      (node (ref "P42") (pin "1") (pinfunction "1_1") (pintype "passive"))
      (node (ref "P44") (pin "1") (pinfunction "1_1") (pintype "passive"))
      (node (ref "P45") (pin "1") (pinfunction "1_1") (pintype "passive"))
      (node (ref "P46") (pin "1") (pinfunction "1_1") (pintype "passive"))
      (node (ref "P47") (pin "1") (pinfunction "1_1") (pintype "passive"))
      (node (ref "P48") (pin "1") (pinfunction "1_1") (pintype "passive"))
      (node (ref "P5") (pin "1") (pinfunction "1_1") (pintype "passive"))
      (node (ref "P6") (pin "1") (pinfunction "1_1") (pintype "passive"))
      (node (ref "P7") (pin "1") (pinfunction "1_1") (pintype "passive"))
      (node (ref "P8") (pin "1") (pinfunction "1_1") (pintype "passive"))
      (node (ref "P9") (pin "1") (pinfunction "1_1") (pintype "passive"))
    )
    (net (code "67") (name "unconnected-(P1-Pad3)") (class "Default")
      (node (ref "P1") (pin "3") (pinfunction "3_3") (pintype "passive"))
    )
    (net (code "68") (name "unconnected-(P2-Pad3)") (class "Default")
      (node (ref "P2") (pin "3") (pinfunction "3_3") (pintype "passive"))
    )
    (net (code "69") (name "unconnected-(P3-Pad3)") (class "Default")
      (node (ref "P3") (pin "3") (pinfunction "3_3") (pintype "passive"))
    )
    (net (code "70") (name "unconnected-(P4-Pad3)") (class "Default")
      (node (ref "P4") (pin "3") (pinfunction "3_3") (pintype "passive"))
    )
    (net (code "71") (name "unconnected-(P5-Pad3)") (class "Default")
      (node (ref "P5") (pin "3") (pinfunction "3_3") (pintype "passive"))
    )
    (net (code "72") (name "unconnected-(P6-Pad3)") (class "Default")
      (node (ref "P6") (pin "3") (pinfunction "3_3") (pintype "passive"))
    )
    (net (code "73") (name "unconnected-(P7-Pad3)") (class "Default")
      (node (ref "P7") (pin "3") (pinfunction "3_3") (pintype "passive"))
    )
    (net (code "74") (name "unconnected-(P8-Pad3)") (class "Default")
      (node (ref "P8") (pin "3") (pinfunction "3_3") (pintype "passive"))
    )
    (net (code "75") (name "unconnected-(P9-Pad3)") (class "Default")
      (node (ref "P9") (pin "3") (pinfunction "3_3") (pintype "passive"))
    )
    (net (code "76") (name "unconnected-(P10-Pad3)") (class "Default")
      (node (ref "P10") (pin "3") (pinfunction "3_3") (pintype "passive"))
    )
    (net (code "77") (name "unconnected-(P11-Pad3)") (class "Default")
      (node (ref "P11") (pin "3") (pinfunction "3_3") (pintype "passive"))
    )
    (net (code "78") (name "unconnected-(P12-Pad3)") (class "Default")
      (node (ref "P12") (pin "3") (pinfunction "3_3") (pintype "passive"))
    )
    (net (code "79") (name "unconnected-(P13-Pad3)") (class "Default")
      (node (ref "P13") (pin "3") (pinfunction "3_3") (pintype "passive"))
    )
    (net (code "80") (name "unconnected-(P14-Pad3)") (class "Default")
      (node (ref "P14") (pin "3") (pinfunction "3_3") (pintype "passive"))
    )
    (net (code "81") (name "unconnected-(P15-Pad3)") (class "Default")
      (node (ref "P15") (pin "3") (pinfunction "3_3") (pintype "passive"))
    )
    (net (code "82") (name "unconnected-(P16-Pad3)") (class "Default")
      (node (ref "P16") (pin "3") (pinfunction "3_3") (pintype "passive"))
    )
    (net (code "83") (name "unconnected-(P17-Pad3)") (class "Default")
      (node (ref "P17") (pin "3") (pinfunction "3_3") (pintype "passive"))
    )
    (net (code "84") (name "unconnected-(P18-Pad3)") (class "Default")
      (node (ref "P18") (pin "3") (pinfunction "3_3") (pintype "passive"))
    )
    (net (code "85") (name "unconnected-(P19-Pad3)") (class "Default")
      (node (ref "P19") (pin "3") (pinfunction "3_3") (pintype "passive"))
    )
    (net (code "86") (name "unconnected-(P20-Pad3)") (class "Default")
      (node (ref "P20") (pin "3") (pinfunction "3_3") (pintype "passive"))
    )
    (net (code "87") (name "unconnected-(P21-Pad3)") (class "Default")
      (node (ref "P21") (pin "3") (pinfunction "3_3") (pintype "passive"))
    )
    (net (code "88") (name "unconnected-(P22-Pad3)") (class "Default")
      (node (ref "P22") (pin "3") (pinfunction "3_3") (pintype "passive"))
    )
    (net (code "89") (name "unconnected-(P23-Pad3)") (class "Default")
      (node (ref "P23") (pin "3") (pinfunction "3_3") (pintype "passive"))
    )
    (net (code "90") (name "unconnected-(P24-Pad3)") (class "Default")
      (node (ref "P24") (pin "3") (pinfunction "3_3") (pintype "passive"))
    )
    (net (code "91") (name "unconnected-(P25-Pad3)") (class "Default")
      (node (ref "P25") (pin "3") (pinfunction "3_3") (pintype "passive"))
    )
    (net (code "92") (name "unconnected-(P26-Pad3)") (class "Default")
      (node (ref "P26") (pin "3") (pinfunction "3_3") (pintype "passive"))
    )
    (net (code "93") (name "unconnected-(P27-Pad3)") (class "Default")
      (node (ref "P27") (pin "3") (pinfunction "3_3") (pintype "passive"))
    )
    (net (code "94") (name "unconnected-(P28-Pad3)") (class "Default")
      (node (ref "P28") (pin "3") (pinfunction "3_3") (pintype "passive"))
    )
    (net (code "95") (name "unconnected-(P29-Pad3)") (class "Default")
      (node (ref "P29") (pin "3") (pinfunction "3_3") (pintype "passive"))
    )
    (net (code "96") (name "unconnected-(P30-Pad3)") (class "Default")
      (node (ref "P30") (pin "3") (pinfunction "3_3") (pintype "passive"))
    )
    (net (code "97") (name "unconnected-(P31-Pad3)") (class "Default")
      (node (ref "P31") (pin "3") (pinfunction "3_3") (pintype "passive"))
    )
    (net (code "98") (name "unconnected-(P32-Pad3)") (class "Default")
      (node (ref "P32") (pin "3") (pinfunction "3_3") (pintype "passive"))
    )
    (net (code "99") (name "unconnected-(P33-Pad3)") (class "Default")
      (node (ref "P33") (pin "3") (pinfunction "3_3") (pintype "passive"))
    )
    (net (code "100") (name "unconnected-(P34-Pad3)") (class "Default")
      (node (ref "P34") (pin "3") (pinfunction "3_3") (pintype "passive"))
    )
    (net (code "101") (name "unconnected-(P35-Pad3)") (class "Default")
      (node (ref "P35") (pin "3") (pinfunction "3_3") (pintype "passive"))
    )
    (net (code "102") (name "unconnected-(P36-Pad3)") (class "Default")
      (node (ref "P36") (pin "3") (pinfunction "3_3") (pintype "passive"))
    )
    (net (code "103") (name "unconnected-(P37-Pad3)") (class "Default")
      (node (ref "P37") (pin "3") (pinfunction "3_3") (pintype "passive"))
    )
    (net (code "104") (name "unconnected-(P41-Pad3)") (class "Default")
      (node (ref "P41") (pin "3") (pinfunction "3_3") (pintype "passive"))
    )
    (net (code "105") (name "unconnected-(P42-Pad3)") (class "Default")
      (node (ref "P42") (pin "3") (pinfunction "3_3") (pintype "passive"))
    )
    (net (code "106") (name "unconnected-(P44-Pad3)") (class "Default")
      (node (ref "P44") (pin "3") (pinfunction "3_3") (pintype "passive"))
    )
    (net (code "107") (name "unconnected-(P45-Pad3)") (class "Default")
      (node (ref "P45") (pin "3") (pinfunction "3_3") (pintype "passive"))
    )
    (net (code "108") (name "unconnected-(P46-Pad3)") (class "Default")
      (node (ref "P46") (pin "3") (pinfunction "3_3") (pintype "passive"))
    )
    (net (code "109") (name "unconnected-(P47-Pad3)") (class "Default")
      (node (ref "P47") (pin "3") (pinfunction "3_3") (pintype "passive"))
    )
    (net (code "110") (name "unconnected-(P48-Pad3)") (class "Default")
      (node (ref "P48") (pin "3") (pinfunction "3_3") (pintype "passive"))
    )
  )
)
